# SterownikZaworu.net
KiCad netlist of a schematic drawn in EAGLE
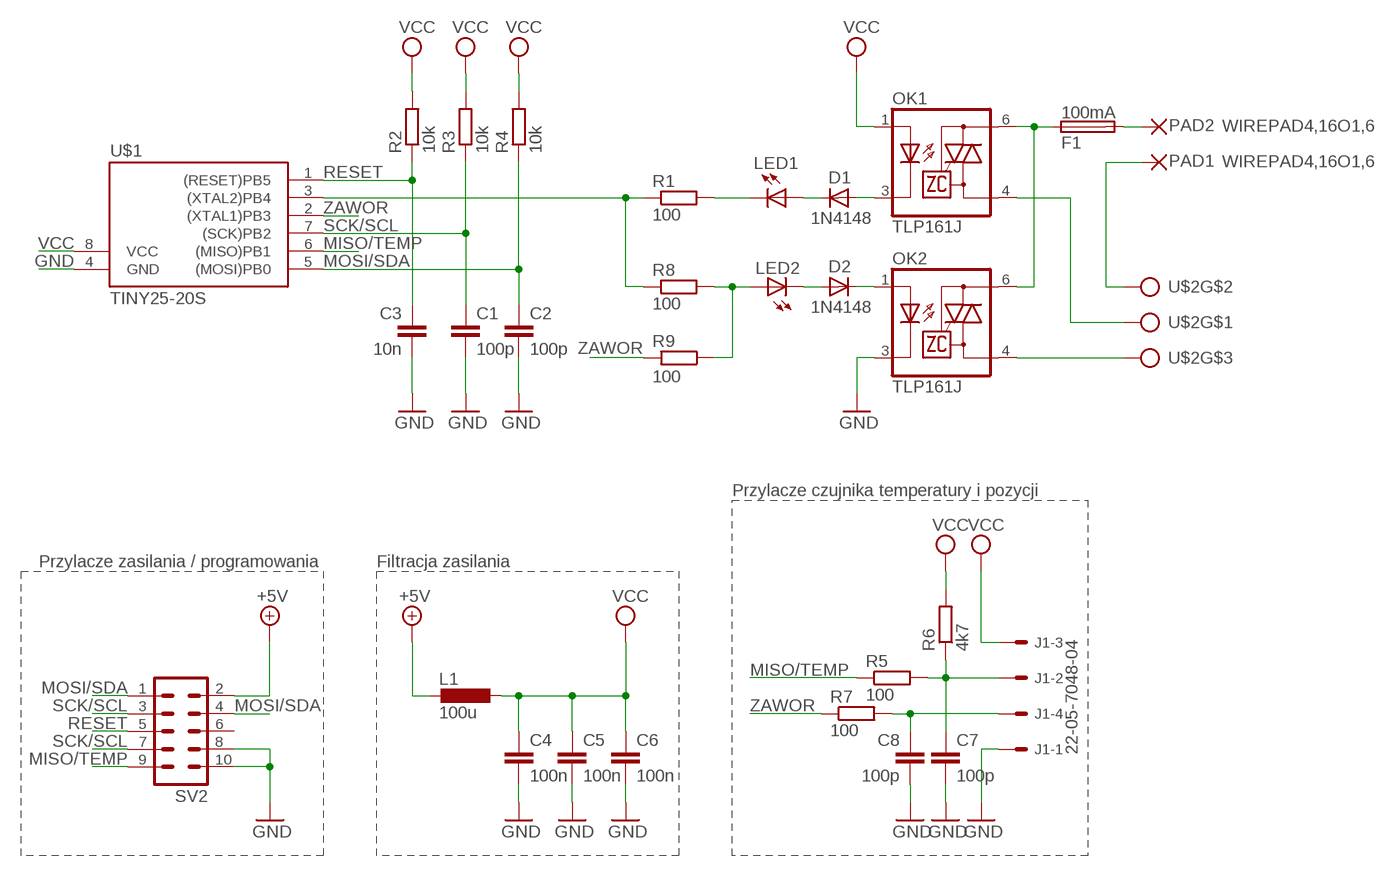
[diagram p0: schematic, sheet 1]

(export (version "E")
  (design (tool "Eeschema 10.0.6"))
  (components
    (comp (ref "C1")
      (value "100p")
      (footprint "eagle-import:C1206")
      (libsource (lib "eagle-import") (part "C-EUC1206"))
    )
    (comp (ref "C2")
      (value "100p")
      (footprint "eagle-import:C1206")
      (libsource (lib "eagle-import") (part "C-EUC1206"))
    )
    (comp (ref "C3")
      (value "10n")
      (footprint "eagle-import:C1206")
      (libsource (lib "eagle-import") (part "C-EUC1206"))
    )
    (comp (ref "C4")
      (value "100n")
      (footprint "eagle-import:C1206")
      (libsource (lib "eagle-import") (part "C-EUC1206"))
    )
    (comp (ref "C5")
      (value "100n")
      (footprint "eagle-import:C1206")
      (libsource (lib "eagle-import") (part "C-EUC1206"))
    )
    (comp (ref "C6")
      (value "100n")
      (footprint "eagle-import:C1206")
      (libsource (lib "eagle-import") (part "C-EUC1206"))
    )
    (comp (ref "C7")
      (value "100p")
      (footprint "eagle-import:C1206")
      (libsource (lib "eagle-import") (part "C-EUC1206"))
    )
    (comp (ref "C8")
      (value "100p")
      (footprint "eagle-import:C1206")
      (libsource (lib "eagle-import") (part "C-EUC1206"))
    )
    (comp (ref "D1")
      (value "1N4148")
      (footprint "eagle-import:MINIMELF")
      (libsource (lib "eagle-import") (part "DIODE-MINIMELF"))
    )
    (comp (ref "D2")
      (value "1N4148")
      (footprint "eagle-import:MINIMELF")
      (libsource (lib "eagle-import") (part "DIODE-MINIMELF"))
    )
    (comp (ref "F1")
      (value "100mA")
      (footprint "eagle-import:F457")
      (libsource (lib "eagle-import") (part "F457"))
    )
    (comp (ref "J1")
      (value "22-05-7048-04")
      (footprint "eagle-import:7395-04")
      (libsource (lib "eagle-import") (part "22-?-0405-7048"))
    )
    (comp (ref "L1")
      (value "100u")
      (footprint "eagle-import:R1210")
      (libsource (lib "eagle-import") (part "L-EUL1210"))
    )
    (comp (ref "LED1")
      (value "LED3MM")
      (footprint "eagle-import:LED3MM")
      (libsource (lib "eagle-import") (part "LED3MM"))
    )
    (comp (ref "LED2")
      (value "LED3MM")
      (footprint "eagle-import:LED3MM")
      (libsource (lib "eagle-import") (part "LED3MM"))
    )
    (comp (ref "OK1")
      (value "TLP161J")
      (footprint "eagle-import:MFP4")
      (libsource (lib "eagle-import") (part "TLP161J"))
    )
    (comp (ref "OK2")
      (value "TLP161J")
      (footprint "eagle-import:MFP4")
      (libsource (lib "eagle-import") (part "TLP161J"))
    )
    (comp (ref "PAD1")
      (value "WIREPAD4,16O1,6")
      (footprint "eagle-import:4,16O1,6")
      (libsource (lib "eagle-import") (part "WIREPAD4,16O1,6"))
    )
    (comp (ref "PAD2")
      (value "WIREPAD4,16O1,6")
      (footprint "eagle-import:4,16O1,6")
      (libsource (lib "eagle-import") (part "WIREPAD4,16O1,6"))
    )
    (comp (ref "R1")
      (value "100")
      (footprint "eagle-import:R1206")
      (libsource (lib "eagle-import") (part "R-EU_R1206"))
    )
    (comp (ref "R2")
      (value "10k")
      (footprint "eagle-import:R1206")
      (libsource (lib "eagle-import") (part "R-EU_R1206"))
    )
    (comp (ref "R3")
      (value "10k")
      (footprint "eagle-import:R1206")
      (libsource (lib "eagle-import") (part "R-EU_R1206"))
    )
    (comp (ref "R4")
      (value "10k")
      (footprint "eagle-import:R1206")
      (libsource (lib "eagle-import") (part "R-EU_R1206"))
    )
    (comp (ref "R5")
      (value "100")
      (footprint "eagle-import:R1206")
      (libsource (lib "eagle-import") (part "R-EU_R1206"))
    )
    (comp (ref "R6")
      (value "4k7")
      (footprint "eagle-import:R1206")
      (libsource (lib "eagle-import") (part "R-EU_R1206"))
    )
    (comp (ref "R7")
      (value "100")
      (footprint "eagle-import:R1206")
      (libsource (lib "eagle-import") (part "R-EU_R1206"))
    )
    (comp (ref "R8")
      (value "100")
      (footprint "eagle-import:R1206")
      (libsource (lib "eagle-import") (part "R-EU_R1206"))
    )
    (comp (ref "R9")
      (value "100")
      (footprint "eagle-import:R1206")
      (libsource (lib "eagle-import") (part "R-EU_R1206"))
    )
    (comp (ref "SV2")
      (value "ML10L")
      (footprint "eagle-import:ML10L")
      (libsource (lib "eagle-import") (part "ML10L"))
    )
    (comp (ref "U$1")
      (value "TINY25-20S")
      (footprint "eagle-import:SOIC8")
      (libsource (lib "eagle-import") (part "TINY25S-20"))
    )
    (comp (ref "U$2")
      (value "AK3001-3")
      (footprint "eagle-import:AK3001-3")
      (libsource (lib "eagle-import") (part "AK3001-3"))
    )
  )
  (nets
    (net (code "1") (name "+5V") (class "Default")
      (node (ref "L1") (pin "2") (pinfunction "2_2") (pintype "passive"))
      (node (ref "SV2") (pin "2") (pinfunction "2_2") (pintype "passive"))
    )
    (net (code "2") (name "/MISO{slash}TEMP") (class "Default")
      (node (ref "R5") (pin "1") (pinfunction "1_1") (pintype "passive"))
      (node (ref "SV2") (pin "9") (pinfunction "9_9") (pintype "passive"))
      (node (ref "U$1") (pin "6") (pinfunction "(MISO)PB1_6") (pintype "bidirectional"))
    )
    (net (code "3") (name "/MOSI{slash}SDA") (class "Default")
      (node (ref "C2") (pin "1") (pinfunction "1_1") (pintype "passive"))
      (node (ref "R4") (pin "1") (pinfunction "1_1") (pintype "passive"))
      (node (ref "SV2") (pin "1") (pinfunction "1_1") (pintype "passive"))
      (node (ref "SV2") (pin "4") (pinfunction "4_4") (pintype "passive"))
      (node (ref "U$1") (pin "5") (pinfunction "(MOSI)PB0_5") (pintype "bidirectional"))
    )
    (net (code "4") (name "/RESET") (class "Default")
      (node (ref "C3") (pin "1") (pinfunction "1_1") (pintype "passive"))
      (node (ref "R2") (pin "1") (pinfunction "1_1") (pintype "passive"))
      (node (ref "SV2") (pin "5") (pinfunction "5_5") (pintype "passive"))
      (node (ref "U$1") (pin "1") (pinfunction "(RESET)PB5_1") (pintype "bidirectional"))
    )
    (net (code "5") (name "/SCK{slash}SCL") (class "Default")
      (node (ref "C1") (pin "1") (pinfunction "1_1") (pintype "passive"))
      (node (ref "R3") (pin "1") (pinfunction "1_1") (pintype "passive"))
      (node (ref "SV2") (pin "3") (pinfunction "3_3") (pintype "passive"))
      (node (ref "SV2") (pin "7") (pinfunction "7_7") (pintype "passive"))
      (node (ref "U$1") (pin "7") (pinfunction "(SCK)PB2_7") (pintype "bidirectional"))
    )
    (net (code "6") (name "/ZAWOR") (class "Default")
      (node (ref "R7") (pin "1") (pinfunction "1_1") (pintype "passive"))
      (node (ref "R9") (pin "2") (pinfunction "2_2") (pintype "passive"))
      (node (ref "U$1") (pin "2") (pinfunction "(XTAL1)PB3_2") (pintype "bidirectional"))
    )
    (net (code "7") (name "GND") (class "Default")
      (node (ref "C1") (pin "2") (pinfunction "2_2") (pintype "passive"))
      (node (ref "C2") (pin "2") (pinfunction "2_2") (pintype "passive"))
      (node (ref "C3") (pin "2") (pinfunction "2_2") (pintype "passive"))
      (node (ref "C4") (pin "2") (pinfunction "2_2") (pintype "passive"))
      (node (ref "C5") (pin "2") (pinfunction "2_2") (pintype "passive"))
      (node (ref "C6") (pin "2") (pinfunction "2_2") (pintype "passive"))
      (node (ref "C7") (pin "2") (pinfunction "2_2") (pintype "passive"))
      (node (ref "C8") (pin "2") (pinfunction "2_2") (pintype "passive"))
      (node (ref "J1") (pin "1") (pinfunction "S_1") (pintype "passive"))
      (node (ref "OK2") (pin "3") (pinfunction "C_3") (pintype "passive"))
      (node (ref "SV2") (pin "10") (pinfunction "10_10") (pintype "passive"))
      (node (ref "SV2") (pin "8") (pinfunction "8_8") (pintype "passive"))
      (node (ref "U$1") (pin "4") (pinfunction "GND_4") (pintype "power_in"))
    )
    (net (code "8") (name "Net-(D1-PadC)") (class "Default")
      (node (ref "D1") (pin "C") (pinfunction "C_C") (pintype "passive"))
      (node (ref "LED1") (pin "A") (pinfunction "A_A") (pintype "passive"))
    )
    (net (code "9") (name "Net-(J1B-S)") (class "Default")
      (node (ref "C7") (pin "1") (pinfunction "1_1") (pintype "passive"))
      (node (ref "J1") (pin "2") (pinfunction "S_2") (pintype "passive"))
      (node (ref "R5") (pin "2") (pinfunction "2_2") (pintype "passive"))
      (node (ref "R6") (pin "1") (pinfunction "1_1") (pintype "passive"))
    )
    (net (code "10") (name "Net-(J1D-S)") (class "Default")
      (node (ref "C8") (pin "1") (pinfunction "1_1") (pintype "passive"))
      (node (ref "J1") (pin "4") (pinfunction "S_4") (pintype "passive"))
      (node (ref "R7") (pin "2") (pinfunction "2_2") (pintype "passive"))
    )
    (net (code "11") (name "Net-(LED1-C)") (class "Default")
      (node (ref "LED1") (pin "K") (pinfunction "C_K") (pintype "passive"))
      (node (ref "R1") (pin "2") (pinfunction "2_2") (pintype "passive"))
    )
    (net (code "12") (name "Net-(LED2-C)") (class "Default")
      (node (ref "D2") (pin "A") (pinfunction "A_A") (pintype "passive"))
      (node (ref "LED2") (pin "K") (pinfunction "C_K") (pintype "passive"))
    )
    (net (code "13") (name "Net-(LED2-PadA)") (class "Default")
      (node (ref "LED2") (pin "A") (pinfunction "A_A") (pintype "passive"))
      (node (ref "R8") (pin "2") (pinfunction "2_2") (pintype "passive"))
      (node (ref "R9") (pin "1") (pinfunction "1_1") (pintype "passive"))
    )
    (net (code "14") (name "Net-(OK1-A1)") (class "Default")
      (node (ref "OK1") (pin "4") (pinfunction "A1_4") (pintype "passive"))
      (node (ref "U$2") (pin "P$1") (pinfunction "KL_P$1") (pintype "passive"))
      (node (ref "U$2") (pin "P$2") (pinfunction "KL_P$2") (pintype "passive"))
    )
    (net (code "15") (name "Net-(OK1-A2)") (class "Default")
      (node (ref "F1") (pin "1") (pinfunction "1_1") (pintype "passive"))
      (node (ref "OK1") (pin "6") (pinfunction "A2_6") (pintype "passive"))
      (node (ref "OK2") (pin "6") (pinfunction "A2_6") (pintype "passive"))
    )
    (net (code "16") (name "Net-(OK1-C)") (class "Default")
      (node (ref "D1") (pin "A") (pinfunction "A_A") (pintype "passive"))
      (node (ref "OK1") (pin "3") (pinfunction "C_3") (pintype "passive"))
    )
    (net (code "17") (name "Net-(OK2-A)") (class "Default")
      (node (ref "D2") (pin "C") (pinfunction "C_C") (pintype "passive"))
      (node (ref "OK2") (pin "1") (pinfunction "A_1") (pintype "passive"))
    )
    (net (code "18") (name "Net-(OK2-A1)") (class "Default")
      (node (ref "OK2") (pin "4") (pinfunction "A1_4") (pintype "passive"))
      (node (ref "U$2") (pin "P$5") (pinfunction "KL_P$5") (pintype "passive"))
      (node (ref "U$2") (pin "P$6") (pinfunction "KL_P$6") (pintype "passive"))
    )
    (net (code "19") (name "Net-(PAD1-P)") (class "Default")
      (node (ref "PAD1") (pin "1") (pinfunction "P_1") (pintype "passive"))
      (node (ref "U$2") (pin "P$3") (pinfunction "KL_P$3") (pintype "passive"))
      (node (ref "U$2") (pin "P$4") (pinfunction "KL_P$4") (pintype "passive"))
    )
    (net (code "20") (name "Net-(PAD2-P)") (class "Default")
      (node (ref "F1") (pin "2") (pinfunction "2_2") (pintype "passive"))
      (node (ref "PAD2") (pin "1") (pinfunction "P_1") (pintype "passive"))
    )
    (net (code "21") (name "Net-(U$1-(XTAL2)PB4)") (class "Default")
      (node (ref "R1") (pin "1") (pinfunction "1_1") (pintype "passive"))
      (node (ref "R8") (pin "1") (pinfunction "1_1") (pintype "passive"))
      (node (ref "U$1") (pin "3") (pinfunction "(XTAL2)PB4_3") (pintype "bidirectional"))
    )
    (net (code "22") (name "VCC") (class "Default")
      (node (ref "C4") (pin "1") (pinfunction "1_1") (pintype "passive"))
      (node (ref "C5") (pin "1") (pinfunction "1_1") (pintype "passive"))
      (node (ref "C6") (pin "1") (pinfunction "1_1") (pintype "passive"))
      (node (ref "J1") (pin "3") (pinfunction "S_3") (pintype "passive"))
      (node (ref "L1") (pin "1") (pinfunction "1_1") (pintype "passive"))
      (node (ref "OK1") (pin "1") (pinfunction "A_1") (pintype "passive"))
      (node (ref "R2") (pin "2") (pinfunction "2_2") (pintype "passive"))
      (node (ref "R3") (pin "2") (pinfunction "2_2") (pintype "passive"))
      (node (ref "R4") (pin "2") (pinfunction "2_2") (pintype "passive"))
      (node (ref "R6") (pin "2") (pinfunction "2_2") (pintype "passive"))
      (node (ref "U$1") (pin "8") (pinfunction "VCC_8") (pintype "power_in"))
    )
    (net (code "23") (name "unconnected-(SV2-Pad6)") (class "Default")
      (node (ref "SV2") (pin "6") (pinfunction "6_6") (pintype "passive"))
    )
  )
)
